# 2.net
KiCad netlist of a schematic drawn in Altium Designer
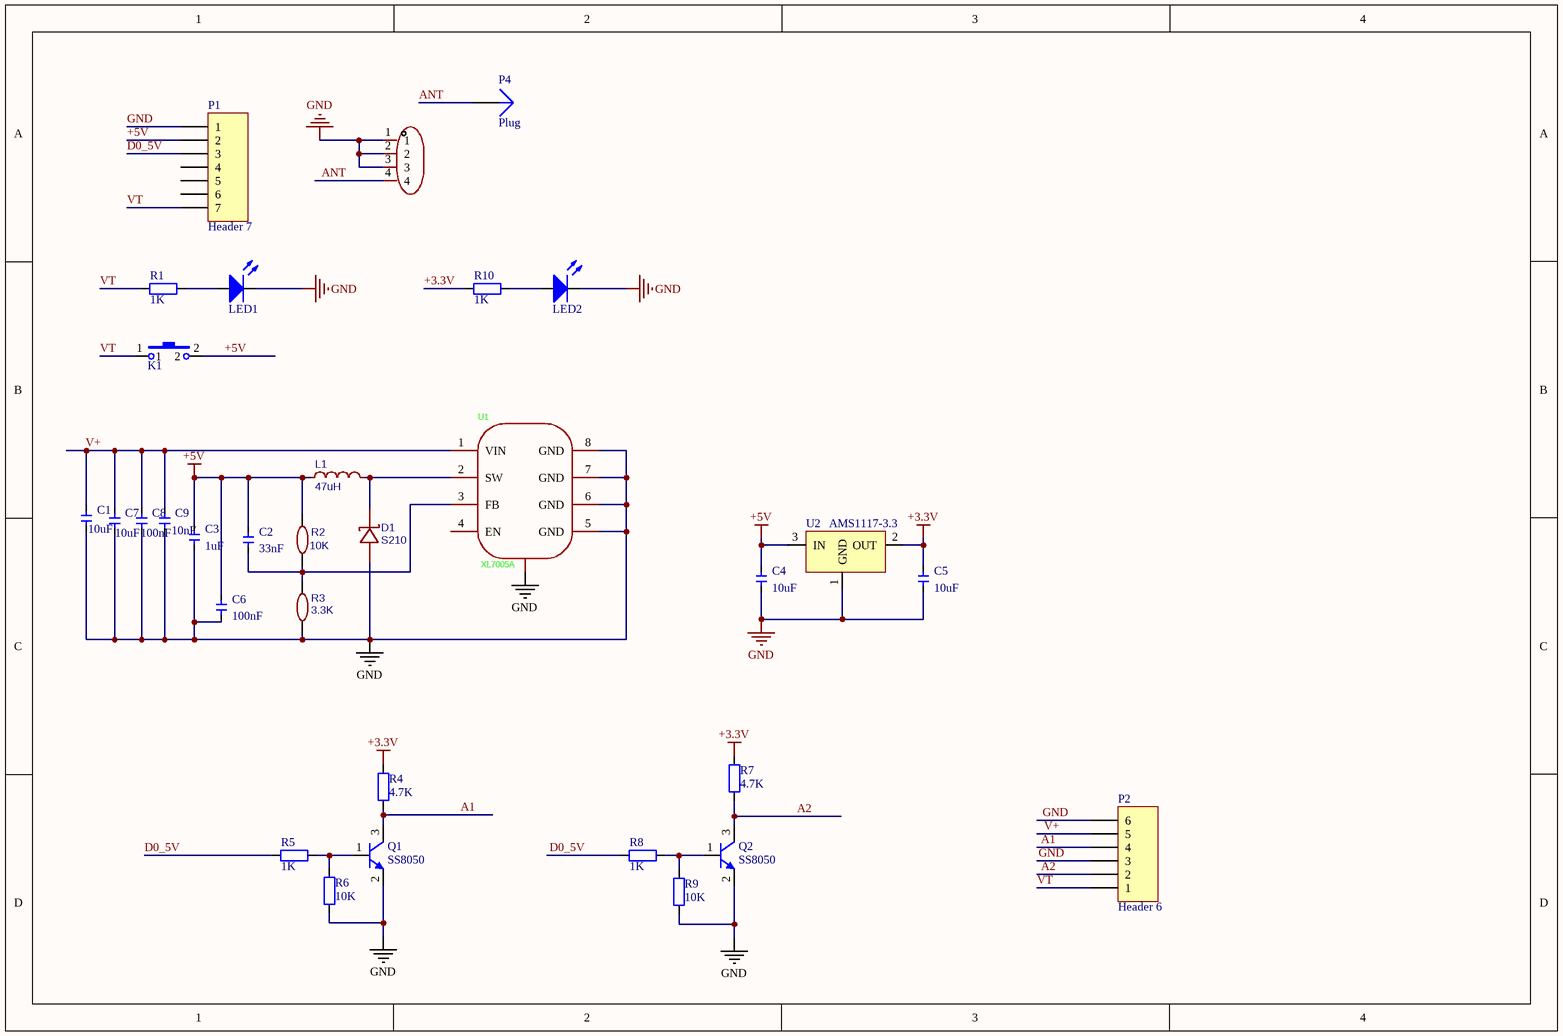
[diagram p0: 遥控2.SchDoc]

(export (version "E")
  (design (tool "Eeschema 10.0.6"))
  (components
    (comp (ref "C1")
      (value "10uF")
      (footprint "0805")
      (description "无极性电容")
      (fields (field (name "PUBLISHER") "Altium Limited"))
      (libsource (lib "Arrowy_Racing") (part "Cap"))
    )
    (comp (ref "C2")
      (value "33nF")
      (footprint "CAP-0603")
      (description "无极性电容")
      (fields (field (name "PUBLISHER") "Altium Limited"))
      (libsource (lib "Arrowy_Racing") (part "Cap"))
    )
    (comp (ref "C3")
      (value "1uF")
      (footprint "CAP-0603")
      (description "无极性电容")
      (fields (field (name "PUBLISHER") "Altium Limited"))
      (libsource (lib "Arrowy_Racing") (part "Cap"))
    )
    (comp (ref "C4")
      (value "10uF")
      (footprint "CAP-0603")
      (description "无极性电容")
      (fields (field (name "PUBLISHER") "Altium Limited"))
      (libsource (lib "Arrowy_Racing") (part "Cap"))
    )
    (comp (ref "C5")
      (value "10uF")
      (footprint "CAP-0603")
      (description "无极性电容")
      (fields (field (name "PUBLISHER") "Altium Limited"))
      (libsource (lib "Arrowy_Racing") (part "Cap"))
    )
    (comp (ref "C6")
      (value "100nF")
      (footprint "CAP-0603")
      (description "无极性电容")
      (fields (field (name "PUBLISHER") "Altium Limited"))
      (libsource (lib "Arrowy_Racing") (part "Cap"))
    )
    (comp (ref "C7")
      (value "10uF")
      (footprint "0805")
      (description "无极性电容")
      (fields (field (name "PUBLISHER") "Altium Limited"))
      (libsource (lib "Arrowy_Racing") (part "Cap"))
    )
    (comp (ref "C8")
      (value "100nF")
      (footprint "0805")
      (description "无极性电容")
      (fields (field (name "PUBLISHER") "Altium Limited"))
      (libsource (lib "Arrowy_Racing") (part "Cap"))
    )
    (comp (ref "C9")
      (value "10nF")
      (footprint "0805")
      (description "无极性电容")
      (fields (field (name "PUBLISHER") "Altium Limited"))
      (libsource (lib "Arrowy_Racing") (part "Cap"))
    )
    (comp (ref "D1")
      (value "S210")
      (footprint "SOD-123")
      (fields (field (name "MANUFACTURER PART") "B340A") (field (name "MANUFACTURER") "MDD"))
      (libsource (lib "altium-import") (part "root_3_B340A_"))
    )
    (comp (ref "K1")
      (value "SW-PB")
      (footprint "SW-SMD_L3.9-W3.0-P4.45")
      (description "微动开关")
      (fields (field (name "SUPPLITER PART") "C961737") (field (name "PUBLISHER") "Altium Limited"))
      (libsource (lib "Arrowy_Racing") (part "SW-PB"))
    )
    (comp (ref "L1")
      (value "47uH")
      (footprint "IND-SMD_L4.0-W4.0_FNR4012S")
      (fields (field (name "MANUFACTURER") "SXN") (field (name "MANUFACTURER PART") "SMDRI127-680MT"))
      (libsource (lib "altium-import") (part "root_0_68uH_"))
    )
    (comp (ref "LED1")
      (value "LED")
      (footprint "LED_0805")
      (description "发光二极管")
      (fields (field (name "PUBLISHER") "Altium Limited"))
      (libsource (lib "Arrowy_Racing") (part "LED"))
    )
    (comp (ref "LED2")
      (value "LED")
      (footprint "LED_0805")
      (description "发光二极管")
      (fields (field (name "PUBLISHER") "Altium Limited"))
      (libsource (lib "Arrowy_Racing") (part "LED"))
    )
    (comp (ref "P1")
      (value "Header 7")
      (footprint "HDR1X7")
      (description "Header, 7-Pin")
      (fields (field (name "PUBLISHER") "Altium Limited"))
      (libsource (lib "Miscellaneous Connectors") (part "Header 7"))
    )
    (comp (ref "P2")
      (value "Header 6")
      (footprint "HDR1X6")
      (description "Header, 6-Pin")
      (fields (field (name "PUBLISHER") "Altium Limited"))
      (libsource (lib "Miscellaneous Connectors") (part "Header 6"))
    )
    (comp (ref "P4")
      (value "Plug")
      (footprint "HEADER_1")
      (description "安装孔")
      (fields (field (name "PUBLISHER") "Altium Limited"))
      (libsource (lib "Arrowy_Racing") (part "Plug"))
    )
    (comp (ref "Q1")
      (value "SS8050")
      (footprint "SOT-23")
      (description "NPN贴片三极管")
      (fields (field (name "PUBLISHER") "Altium Limited"))
      (libsource (lib "Arrowy_Racing") (part "SS8050"))
    )
    (comp (ref "Q2")
      (value "SS8050")
      (footprint "SOT-23")
      (description "NPN贴片三极管")
      (fields (field (name "PUBLISHER") "Altium Limited"))
      (libsource (lib "Arrowy_Racing") (part "SS8050"))
    )
    (comp (ref "R1")
      (value "1K")
      (footprint "0603 - duplicate1")
      (description "贴片电阻")
      (fields (field (name "PUBLISHER") "Altium Limited"))
      (libsource (lib "") (part "Res_1"))
    )
    (comp (ref "R2")
      (value "10K")
      (footprint "0603 - duplicate1")
      (fields (field (name "MANUFACTURER") "UniOhm") (field (name "MANUFACTURER PART") "0603WAF1001T5E"))
      (libsource (lib "altium-import") (part "root_1_1K_"))
    )
    (comp (ref "R3")
      (value "3.3K")
      (footprint "0603 - duplicate1")
      (fields (field (name "MANUFACTURER") "UniOhm") (field (name "MANUFACTURER PART") "0603WAF3001T5E"))
      (libsource (lib "altium-import") (part "root_3_3K_"))
    )
    (comp (ref "R4")
      (value "4.7K")
      (footprint "0603 - duplicate1")
      (description "贴片电阻")
      (fields (field (name "PUBLISHER") "Altium Limited"))
      (libsource (lib "") (part "Res_3"))
    )
    (comp (ref "R5")
      (value "1K")
      (footprint "0603 - duplicate1")
      (description "贴片电阻")
      (fields (field (name "PUBLISHER") "Altium Limited"))
      (libsource (lib "") (part "Res_2"))
    )
    (comp (ref "R6")
      (value "10K")
      (footprint "0603 - duplicate1")
      (description "贴片电阻")
      (fields (field (name "PUBLISHER") "Altium Limited"))
      (libsource (lib "Arrowy_Racing") (part "Res"))
    )
    (comp (ref "R7")
      (value "4.7K")
      (footprint "0603 - duplicate1")
      (description "贴片电阻")
      (fields (field (name "PUBLISHER") "Altium Limited"))
      (libsource (lib "") (part "Res_3"))
    )
    (comp (ref "R8")
      (value "1K")
      (footprint "0603 - duplicate1")
      (description "贴片电阻")
      (fields (field (name "PUBLISHER") "Altium Limited"))
      (libsource (lib "") (part "Res_2"))
    )
    (comp (ref "R9")
      (value "10K")
      (footprint "0603 - duplicate1")
      (description "贴片电阻")
      (fields (field (name "PUBLISHER") "Altium Limited"))
      (libsource (lib "Arrowy_Racing") (part "Res"))
    )
    (comp (ref "R10")
      (value "1K")
      (footprint "0603 - duplicate1")
      (description "贴片电阻")
      (fields (field (name "PUBLISHER") "Altium Limited"))
      (libsource (lib "") (part "Res_1"))
    )
    (comp (ref "RF1")
      (value "6GHz")
      (footprint "CONN-SMD_GT-RF1125A-01G")
      (fields
        (field (name "MANUFACTURER") "G-Switch(品赞)")
        (field (name "MANUFACTURER PART") "GT-RF1125A-01G")
      )
      (libsource (lib "altium-import") (part "root_0_GT-RF1125A-01G_"))
    )
    (comp (ref "U1")
      (value "XL7005A")
      (footprint "SOIC-8_L4.9-W3.9-P1.27-LS6.0-BL-EP3.1-1")
      (fields (field (name "MANUFACTURER") "XLSEMI(芯龙)"))
      (libsource (lib "altium-import") (part "root_0_XL7005A_"))
    )
    (comp (ref "U2")
      (value "AMS1117-3.3")
      (footprint "SOT89")
      (description "3.3V稳压芯片")
      (libsource (lib "Arrowy_Racing") (part "AMS1117"))
    )
  )
  (nets
    (net (code "1") (name "+3.3V") (class "Default")
      (node (ref "C5") (pin "2") (pinfunction "2_2") (pintype "passive"))
      (node (ref "R10") (pin "2") (pinfunction "2_2") (pintype "passive"))
      (node (ref "R4") (pin "1") (pinfunction "1_1") (pintype "passive"))
      (node (ref "R7") (pin "1") (pinfunction "1_1") (pintype "passive"))
      (node (ref "U2") (pin "2") (pinfunction "OUT_2") (pintype "passive"))
    )
    (net (code "2") (name "+5V") (class "Default")
      (node (ref "C2") (pin "2") (pinfunction "2_2") (pintype "passive"))
      (node (ref "C3") (pin "2") (pinfunction "2_2") (pintype "passive"))
      (node (ref "C4") (pin "2") (pinfunction "2_2") (pintype "passive"))
      (node (ref "C6") (pin "2") (pinfunction "2_2") (pintype "passive"))
      (node (ref "K1") (pin "2") (pinfunction "2_2") (pintype "passive"))
      (node (ref "L1") (pin "1") (pinfunction "1_1") (pintype "passive"))
      (node (ref "P1") (pin "2") (pinfunction "2_2") (pintype "passive"))
      (node (ref "R2") (pin "2") (pinfunction "2_2") (pintype "passive"))
      (node (ref "U2") (pin "3") (pinfunction "IN_3") (pintype "passive"))
    )
    (net (code "3") (name "/A1") (class "Default")
      (node (ref "P2") (pin "4") (pinfunction "4_4") (pintype "passive"))
      (node (ref "Q1") (pin "3") (pinfunction "C_3") (pintype "passive"))
      (node (ref "R4") (pin "2") (pinfunction "2_2") (pintype "passive"))
    )
    (net (code "4") (name "/A2") (class "Default")
      (node (ref "P2") (pin "2") (pinfunction "2_2") (pintype "passive"))
      (node (ref "Q2") (pin "3") (pinfunction "C_3") (pintype "passive"))
      (node (ref "R7") (pin "2") (pinfunction "2_2") (pintype "passive"))
    )
    (net (code "5") (name "/ANT") (class "Default")
      (node (ref "P4") (pin "1") (pinfunction "1_1") (pintype "passive"))
      (node (ref "RF1") (pin "4") (pinfunction "4_4") (pintype "passive"))
    )
    (net (code "6") (name "/D0_5V") (class "Default")
      (node (ref "P1") (pin "3") (pinfunction "3_3") (pintype "passive"))
      (node (ref "R5") (pin "1") (pinfunction "1_1") (pintype "passive"))
      (node (ref "R8") (pin "1") (pinfunction "1_1") (pintype "passive"))
    )
    (net (code "7") (name "/V+") (class "Default")
      (node (ref "C1") (pin "2") (pinfunction "2_2") (pintype "passive"))
      (node (ref "C7") (pin "2") (pinfunction "2_2") (pintype "passive"))
      (node (ref "C8") (pin "2") (pinfunction "2_2") (pintype "passive"))
      (node (ref "C9") (pin "2") (pinfunction "2_2") (pintype "passive"))
      (node (ref "P2") (pin "5") (pinfunction "5_5") (pintype "passive"))
      (node (ref "U1") (pin "1") (pinfunction "VIN_1") (pintype "passive"))
    )
    (net (code "8") (name "/VT") (class "Default")
      (node (ref "K1") (pin "1") (pinfunction "1_1") (pintype "passive"))
      (node (ref "P1") (pin "7") (pinfunction "7_7") (pintype "passive"))
      (node (ref "P2") (pin "1") (pinfunction "1_1") (pintype "passive"))
      (node (ref "R1") (pin "2") (pinfunction "2_2") (pintype "passive"))
    )
    (net (code "9") (name "GND") (class "Default")
      (node (ref "C1") (pin "1") (pinfunction "1_1") (pintype "passive"))
      (node (ref "C3") (pin "1") (pinfunction "1_1") (pintype "passive"))
      (node (ref "C4") (pin "1") (pinfunction "1_1") (pintype "passive"))
      (node (ref "C5") (pin "1") (pinfunction "1_1") (pintype "passive"))
      (node (ref "C6") (pin "1") (pinfunction "1_1") (pintype "passive"))
      (node (ref "C7") (pin "1") (pinfunction "1_1") (pintype "passive"))
      (node (ref "C8") (pin "1") (pinfunction "1_1") (pintype "passive"))
      (node (ref "C9") (pin "1") (pinfunction "1_1") (pintype "passive"))
      (node (ref "D1") (pin "2") (pinfunction "A_2") (pintype "passive"))
      (node (ref "LED1") (pin "2") (pinfunction "K_2") (pintype "passive"))
      (node (ref "LED2") (pin "2") (pinfunction "K_2") (pintype "passive"))
      (node (ref "P1") (pin "1") (pinfunction "1_1") (pintype "passive"))
      (node (ref "P2") (pin "3") (pinfunction "3_3") (pintype "passive"))
      (node (ref "P2") (pin "6") (pinfunction "6_6") (pintype "passive"))
      (node (ref "Q1") (pin "2") (pinfunction "E_2") (pintype "passive"))
      (node (ref "Q2") (pin "2") (pinfunction "E_2") (pintype "passive"))
      (node (ref "R3") (pin "2") (pinfunction "2_2") (pintype "passive"))
      (node (ref "R6") (pin "1") (pinfunction "1_1") (pintype "passive"))
      (node (ref "R9") (pin "1") (pinfunction "1_1") (pintype "passive"))
      (node (ref "RF1") (pin "1") (pinfunction "1_1") (pintype "passive"))
      (node (ref "RF1") (pin "2") (pinfunction "2_2") (pintype "passive"))
      (node (ref "RF1") (pin "3") (pinfunction "3_3") (pintype "passive"))
      (node (ref "U1") (pin "5") (pinfunction "GND_5") (pintype "passive"))
      (node (ref "U1") (pin "6") (pinfunction "GND_6") (pintype "passive"))
      (node (ref "U1") (pin "7") (pinfunction "GND_7") (pintype "passive"))
      (node (ref "U1") (pin "8") (pinfunction "GND_8") (pintype "passive"))
      (node (ref "U1") (pin "9") (pinfunction "9_9") (pintype "passive"))
      (node (ref "U2") (pin "1") (pinfunction "GND_1") (pintype "passive"))
    )
    (net (code "10") (name "Net-(D1-K)") (class "Default")
      (node (ref "D1") (pin "1") (pinfunction "K_1") (pintype "passive"))
      (node (ref "L1") (pin "2") (pinfunction "2_2") (pintype "passive"))
      (node (ref "U1") (pin "2") (pinfunction "SW_2") (pintype "passive"))
    )
    (net (code "11") (name "Net-(LED1-A)") (class "Default")
      (node (ref "LED1") (pin "1") (pinfunction "A_1") (pintype "passive"))
      (node (ref "R1") (pin "1") (pinfunction "1_1") (pintype "passive"))
    )
    (net (code "12") (name "Net-(LED2-A)") (class "Default")
      (node (ref "LED2") (pin "1") (pinfunction "A_1") (pintype "passive"))
      (node (ref "R10") (pin "1") (pinfunction "1_1") (pintype "passive"))
    )
    (net (code "13") (name "Net-(Q1-B)") (class "Default")
      (node (ref "Q1") (pin "1") (pinfunction "B_1") (pintype "passive"))
      (node (ref "R5") (pin "2") (pinfunction "2_2") (pintype "passive"))
      (node (ref "R6") (pin "2") (pinfunction "2_2") (pintype "passive"))
    )
    (net (code "14") (name "Net-(Q2-B)") (class "Default")
      (node (ref "Q2") (pin "1") (pinfunction "B_1") (pintype "passive"))
      (node (ref "R8") (pin "2") (pinfunction "2_2") (pintype "passive"))
      (node (ref "R9") (pin "2") (pinfunction "2_2") (pintype "passive"))
    )
    (net (code "15") (name "Net-(U1-FB)") (class "Default")
      (node (ref "C2") (pin "1") (pinfunction "1_1") (pintype "passive"))
      (node (ref "R2") (pin "1") (pinfunction "1_1") (pintype "passive"))
      (node (ref "R3") (pin "1") (pinfunction "1_1") (pintype "passive"))
      (node (ref "U1") (pin "3") (pinfunction "FB_3") (pintype "passive"))
    )
    (net (code "16") (name "unconnected-(P1-Pad4)") (class "Default")
      (node (ref "P1") (pin "4") (pinfunction "4_4") (pintype "passive"))
    )
    (net (code "17") (name "unconnected-(P1-Pad5)") (class "Default")
      (node (ref "P1") (pin "5") (pinfunction "5_5") (pintype "passive"))
    )
    (net (code "18") (name "unconnected-(P1-Pad6)") (class "Default")
      (node (ref "P1") (pin "6") (pinfunction "6_6") (pintype "passive"))
    )
    (net (code "19") (name "unconnected-(U1-EN-Pad4)") (class "Default")
      (node (ref "U1") (pin "4") (pinfunction "EN_4") (pintype "passive"))
    )
  )
)
